# sensor.net
KiCad netlist of a schematic drawn in EAGLE
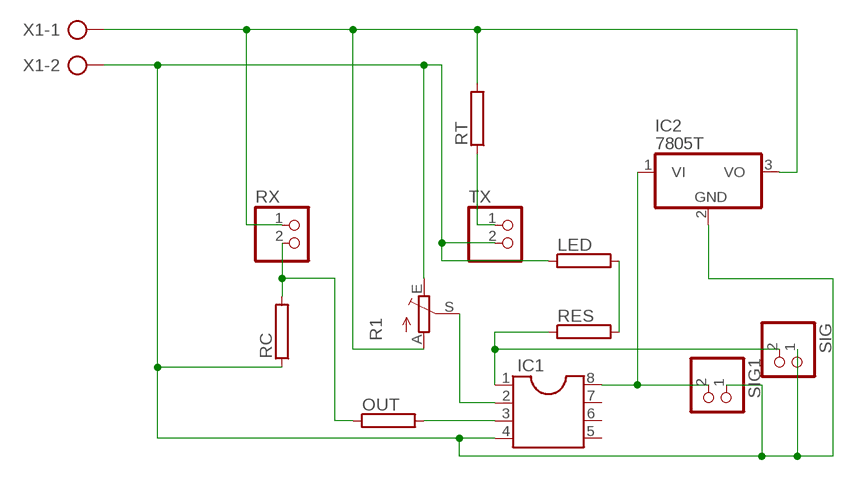
[diagram p0: schematic, sheet 1]

(export (version "E")
  (design (tool "Eeschema 10.0.6"))
  (components
    (comp (ref "IC1")
      (value "DIL8")
      (footprint "eagle-import:DIL08")
      (libsource (lib "eagle-import") (part "DIL8"))
    )
    (comp (ref "IC2")
      (value "7805T")
      (footprint "eagle-import:TO220H")
      (libsource (lib "eagle-import") (part "78T05"))
    )
    (comp (ref "LED")
      (value "RKH208-8R")
      (footprint "eagle-import:KH208R-8")
      (libsource (lib "eagle-import") (part "RKH208-8R"))
    )
    (comp (ref "OUT")
      (value "RKH208-8R")
      (footprint "eagle-import:KH208R-8")
      (libsource (lib "eagle-import") (part "RKH208-8R"))
    )
    (comp (ref "R1")
      (value "TRIM_EU-CA6V")
      (footprint "eagle-import:CA6V")
      (libsource (lib "eagle-import") (part "TRIM_EU-CA6V"))
    )
    (comp (ref "RC")
      (value "RKH208-8R")
      (footprint "eagle-import:KH208R-8")
      (libsource (lib "eagle-import") (part "RKH208-8R"))
    )
    (comp (ref "RES")
      (value "RKH208-8R")
      (footprint "eagle-import:KH208R-8")
      (libsource (lib "eagle-import") (part "RKH208-8R"))
    )
    (comp (ref "RT")
      (value "RKH208-8R")
      (footprint "eagle-import:KH208R-8")
      (libsource (lib "eagle-import") (part "RKH208-8R"))
    )
    (comp (ref "RX")
      (value "PINHD-1X2")
      (footprint "eagle-import:1X02")
      (libsource (lib "eagle-import") (part "PINHD-1X2"))
    )
    (comp (ref "SIG")
      (value "PINHD-1X2")
      (footprint "eagle-import:1X02")
      (libsource (lib "eagle-import") (part "PINHD-1X2"))
    )
    (comp (ref "SIG1")
      (value "PINHD-1X2")
      (footprint "eagle-import:1X02")
      (libsource (lib "eagle-import") (part "PINHD-1X2"))
    )
    (comp (ref "TX")
      (value "PINHD-1X2")
      (footprint "eagle-import:1X02")
      (libsource (lib "eagle-import") (part "PINHD-1X2"))
    )
    (comp (ref "X1")
      (value "AK500/2-H")
      (footprint "eagle-import:AK500_2-H")
      (libsource (lib "eagle-import") (part "AK500/2-H"))
    )
  )
  (nets
    (net (code "1") (name "Net-(IC1-Pad1)") (class "Default")
      (node (ref "IC1") (pin "1") (pinfunction "1_1") (pintype "passive"))
      (node (ref "RES") (pin "1") (pinfunction "1_1") (pintype "passive"))
      (node (ref "SIG") (pin "2") (pinfunction "2_2") (pintype "passive"))
    )
    (net (code "2") (name "Net-(IC1-Pad2)") (class "Default")
      (node (ref "IC1") (pin "2") (pinfunction "2_2") (pintype "passive"))
      (node (ref "R1") (pin "S") (pinfunction "S_S") (pintype "passive"))
    )
    (net (code "3") (name "Net-(IC1-Pad3)") (class "Default")
      (node (ref "IC1") (pin "3") (pinfunction "3_3") (pintype "passive"))
      (node (ref "OUT") (pin "2") (pinfunction "2_2") (pintype "passive"))
    )
    (net (code "4") (name "Net-(IC2-GND)") (class "Default")
      (node (ref "IC1") (pin "4") (pinfunction "4_4") (pintype "passive"))
      (node (ref "IC2") (pin "2") (pinfunction "GND_2") (pintype "passive"))
      (node (ref "LED") (pin "1") (pinfunction "1_1") (pintype "passive"))
      (node (ref "R1") (pin "E") (pinfunction "E_E") (pintype "passive"))
      (node (ref "RC") (pin "1") (pinfunction "1_1") (pintype "passive"))
      (node (ref "SIG") (pin "1") (pinfunction "1_1") (pintype "passive"))
      (node (ref "SIG1") (pin "1") (pinfunction "1_1") (pintype "passive"))
      (node (ref "TX") (pin "2") (pinfunction "2_2") (pintype "passive"))
      (node (ref "X1") (pin "2") (pinfunction "KL_2") (pintype "passive"))
    )
    (net (code "5") (name "Net-(IC2-VI)") (class "Default")
      (node (ref "IC1") (pin "8") (pinfunction "8_8") (pintype "passive"))
      (node (ref "IC2") (pin "1") (pinfunction "VI_1") (pintype "input"))
      (node (ref "SIG1") (pin "2") (pinfunction "2_2") (pintype "passive"))
    )
    (net (code "6") (name "Net-(IC2-VO)") (class "Default")
      (node (ref "IC2") (pin "3") (pinfunction "VO_3") (pintype "passive"))
      (node (ref "R1") (pin "A") (pinfunction "A_A") (pintype "passive"))
      (node (ref "RT") (pin "2") (pinfunction "2_2") (pintype "passive"))
      (node (ref "RX") (pin "1") (pinfunction "1_1") (pintype "passive"))
      (node (ref "X1") (pin "1") (pinfunction "KL_1") (pintype "passive"))
    )
    (net (code "7") (name "Net-(LED-Pad2)") (class "Default")
      (node (ref "LED") (pin "2") (pinfunction "2_2") (pintype "passive"))
      (node (ref "RES") (pin "2") (pinfunction "2_2") (pintype "passive"))
    )
    (net (code "8") (name "Net-(OUT-Pad1)") (class "Default")
      (node (ref "OUT") (pin "1") (pinfunction "1_1") (pintype "passive"))
      (node (ref "RC") (pin "2") (pinfunction "2_2") (pintype "passive"))
      (node (ref "RX") (pin "2") (pinfunction "2_2") (pintype "passive"))
    )
    (net (code "9") (name "Net-(RT-Pad1)") (class "Default")
      (node (ref "RT") (pin "1") (pinfunction "1_1") (pintype "passive"))
      (node (ref "TX") (pin "1") (pinfunction "1_1") (pintype "passive"))
    )
    (net (code "10") (name "unconnected-(IC1-Pad5)") (class "Default")
      (node (ref "IC1") (pin "5") (pinfunction "5_5") (pintype "passive"))
    )
    (net (code "11") (name "unconnected-(IC1-Pad6)") (class "Default")
      (node (ref "IC1") (pin "6") (pinfunction "6_6") (pintype "passive"))
    )
    (net (code "12") (name "unconnected-(IC1-Pad7)") (class "Default")
      (node (ref "IC1") (pin "7") (pinfunction "7_7") (pintype "passive"))
    )
  )
)
